# Trigger.net
KiCad netlist of a schematic drawn in Altium Designer
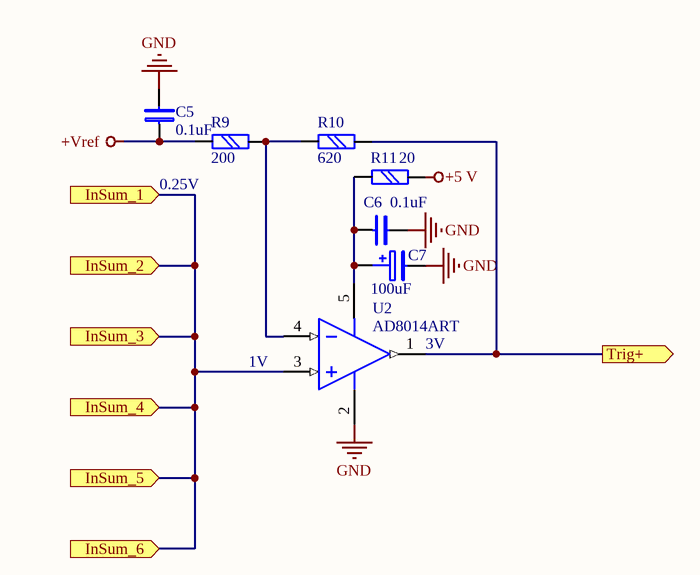
[diagram p0: Trigger.SchDoc]

(export (version "E")
  (design (tool "Eeschema 10.0.6"))
  (components
    (comp (ref "C5") (value "0.1uF") (footprint "chip0603") (libsource (lib "vDevice") (part "C")))
    (comp (ref "C6") (value "0.1uF") (footprint "chip0603") (libsource (lib "vDevice") (part "C")))
    (comp (ref "C7") (value "100uF") (footprint "CEL-SMD300") (libsource (lib "vDevice") (part "C POL")))
    (comp (ref "R9") (value "200") (footprint "chip0603") (libsource (lib "vDevice") (part "R")))
    (comp (ref "R10") (value "620") (footprint "chip0603") (libsource (lib "vDevice") (part "R")))
    (comp (ref "R11") (value "20") (footprint "chip0603") (libsource (lib "vDevice") (part "R")))
    (comp (ref "U2")
      (value "AD8014ART")
      (footprint "RT-5")
      (description "Low Cost, 300MHz Voltage Feedback Amplifier")
      (fields (field (name "PUBLISHER") "Altium Limited"))
      (libsource (lib "AD Operational Amplifier") (part "AD8055ART"))
    )
  )
  (nets
    (net (code "1") (name "+5 V") (class "Default")
      (node (ref "R11") (pin "1") (pinfunction "1_1") (pintype "passive"))
    )
    (net (code "2") (name "+Vref") (class "Default")
      (node (ref "C5") (pin "2") (pinfunction "2_2") (pintype "passive"))
      (node (ref "R9") (pin "2") (pinfunction "2_2") (pintype "passive"))
    )
    (net (code "3") (name "/InSum_1") (class "Default")
      (node (ref "U2") (pin "3") (pinfunction "IN+_3") (pintype "input"))
    )
    (net (code "4") (name "/Trig+") (class "Default")
      (node (ref "R10") (pin "2") (pinfunction "2_2") (pintype "passive"))
      (node (ref "U2") (pin "1") (pinfunction "OUT_1") (pintype "output"))
    )
    (net (code "5") (name "GND") (class "Default")
      (node (ref "C5") (pin "1") (pinfunction "1_1") (pintype "passive"))
      (node (ref "C6") (pin "1") (pinfunction "1_1") (pintype "passive"))
      (node (ref "C7") (pin "-") (pinfunction "-_-") (pintype "passive"))
      (node (ref "U2") (pin "2") (pinfunction "V-_2") (pintype "power_in"))
    )
    (net (code "6") (name "Net-(U2-IN-)") (class "Default")
      (node (ref "R10") (pin "1") (pinfunction "1_1") (pintype "passive"))
      (node (ref "R9") (pin "1") (pinfunction "1_1") (pintype "passive"))
      (node (ref "U2") (pin "4") (pinfunction "IN-_4") (pintype "input"))
    )
    (net (code "7") (name "Net-(U2-V+)") (class "Default")
      (node (ref "C6") (pin "2") (pinfunction "2_2") (pintype "passive"))
      (node (ref "C7") (pin "+") (pinfunction "+_+") (pintype "passive"))
      (node (ref "R11") (pin "2") (pinfunction "2_2") (pintype "passive"))
      (node (ref "U2") (pin "5") (pinfunction "V+_5") (pintype "power_in"))
    )
  )
)
